# PCB.net
KiCad netlist of a schematic drawn in Altium Designer
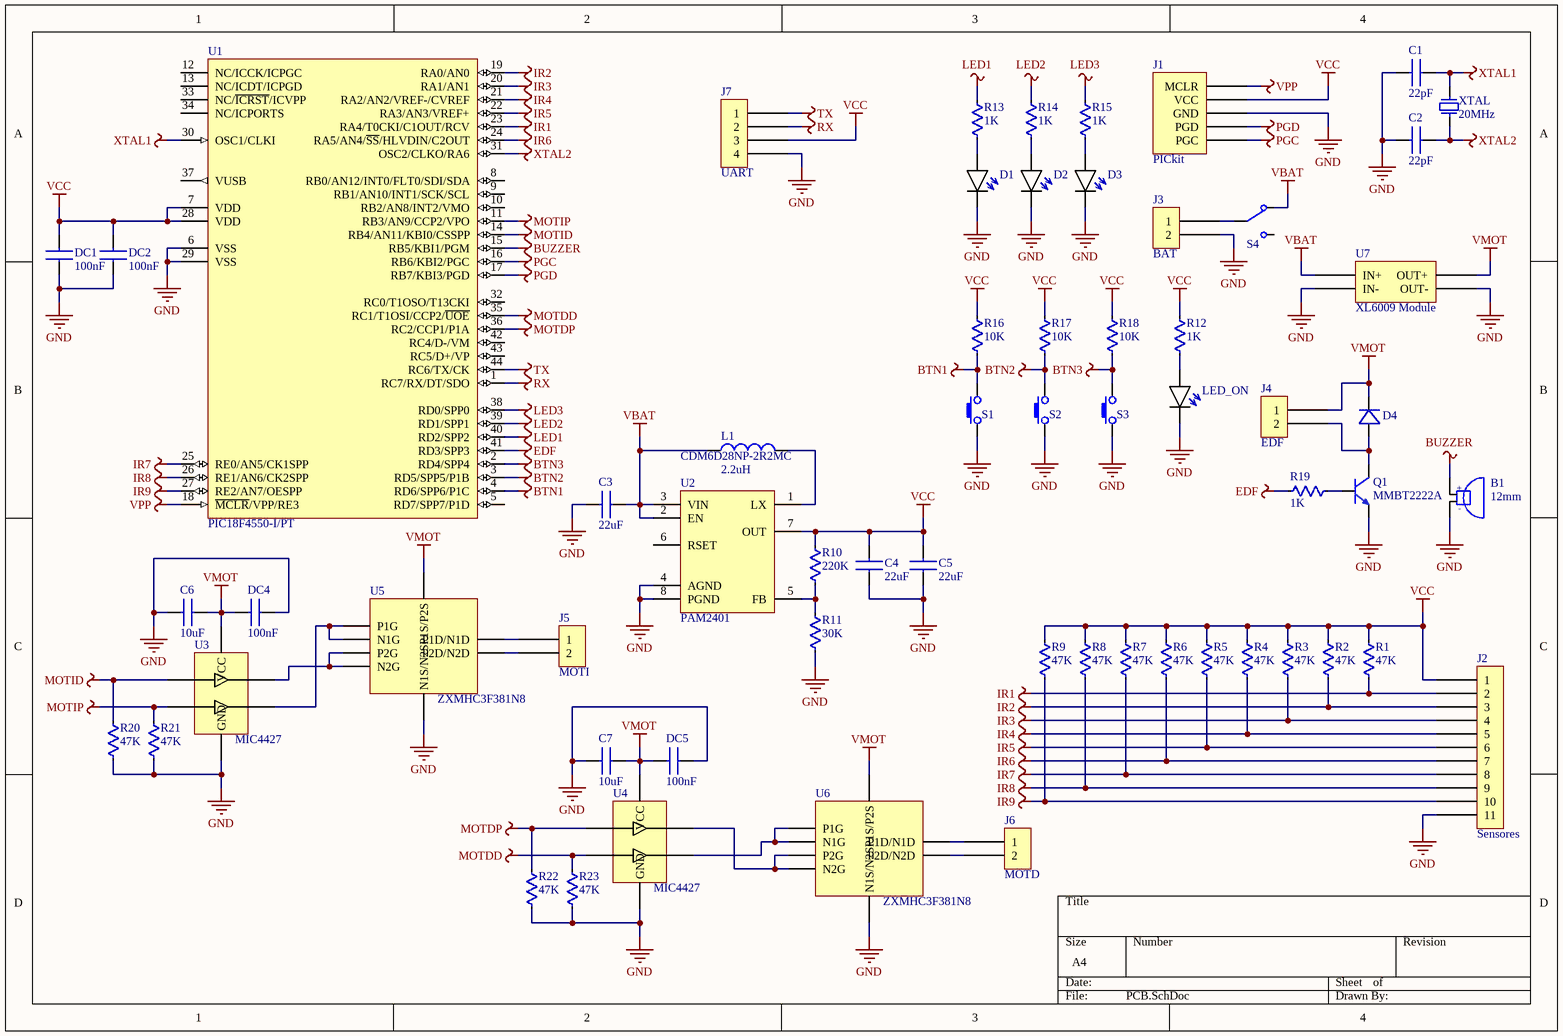
[diagram p0: PCB.SchDoc]

(export (version "E")
  (design (tool "Eeschema 10.0.6"))
  (components
    (comp (ref "B1")
      (value "12mm")
      (footprint "BUZZER-12MM")
      (libsource (lib "AltiumLibrary") (part "BUZZER-ACTIVE"))
    )
    (comp (ref "C1")
      (value "22pF")
      (footprint "C1206")
      (fields (field (name "Comment") "CAP-CER"))
      (libsource (lib "AltiumLibrary") (part "CAP-CER"))
    )
    (comp (ref "C2")
      (value "22pF")
      (footprint "C1206")
      (fields (field (name "Comment") "CAP-CER"))
      (libsource (lib "AltiumLibrary") (part "CAP-CER"))
    )
    (comp (ref "C3")
      (value "22uF")
      (footprint "C1206")
      (fields (field (name "Comment") "CAP-CER"))
      (libsource (lib "AltiumLibrary") (part "CAP-CER"))
    )
    (comp (ref "C4")
      (value "22uF")
      (footprint "C1206")
      (fields (field (name "Comment") "CAP-CER"))
      (libsource (lib "AltiumLibrary") (part "CAP-CER"))
    )
    (comp (ref "C5")
      (value "22uF")
      (footprint "C1206")
      (fields (field (name "Comment") "CAP-CER"))
      (libsource (lib "AltiumLibrary") (part "CAP-CER"))
    )
    (comp (ref "C6")
      (value "10uF")
      (footprint "C1206")
      (fields (field (name "Comment") "CAP-CER"))
      (libsource (lib "AltiumLibrary") (part "CAP-CER"))
    )
    (comp (ref "C7")
      (value "10uF")
      (footprint "C1206")
      (fields (field (name "Comment") "CAP-CER"))
      (libsource (lib "AltiumLibrary") (part "CAP-CER"))
    )
    (comp (ref "D1") (value "LED") (footprint "LED-3MM-RED") (libsource (lib "AltiumLibrary") (part "LED")))
    (comp (ref "D2")
      (value "LED")
      (footprint "LED-3MM-YELLOW")
      (libsource (lib "AltiumLibrary") (part "LED"))
    )
    (comp (ref "D3") (value "LED") (footprint "LED-3MM-GREEN") (libsource (lib "AltiumLibrary") (part "LED")))
    (comp (ref "D4") (value "1N4007") (footprint "DO-214AC") (libsource (lib "AltiumLibrary") (part "DIODE")))
    (comp (ref "DC1")
      (value "100nF")
      (footprint "C1206")
      (fields (field (name "Comment") "CAP-CER"))
      (libsource (lib "AltiumLibrary") (part "CAP-CER"))
    )
    (comp (ref "DC2")
      (value "100nF")
      (footprint "C1206")
      (fields (field (name "Comment") "CAP-CER"))
      (libsource (lib "AltiumLibrary") (part "CAP-CER"))
    )
    (comp (ref "DC4")
      (value "100nF")
      (footprint "C1206")
      (fields (field (name "Comment") "CAP-CER"))
      (libsource (lib "AltiumLibrary") (part "CAP-CER"))
    )
    (comp (ref "DC5")
      (value "100nF")
      (footprint "C1206")
      (fields (field (name "Comment") "CAP-CER"))
      (libsource (lib "AltiumLibrary") (part "CAP-CER"))
    )
    (comp (ref "J1")
      (value "PICkit")
      (footprint "Header 1x5")
      (libsource (lib "AltiumLibrary") (part "PICkit"))
    )
    (comp (ref "J2")
      (value "Sensores")
      (footprint "Header 1x11")
      (libsource (lib "AltiumLibrary") (part "Header 1x11"))
    )
    (comp (ref "J3")
      (value "BAT")
      (footprint "HEADER 1x2")
      (libsource (lib "AltiumLibrary") (part "Header 1x2"))
    )
    (comp (ref "J4")
      (value "EDF")
      (footprint "HEADER 1x2")
      (libsource (lib "AltiumLibrary") (part "Header 1x2"))
    )
    (comp (ref "J5") (value "MOTI") (footprint "HEADER 1x2") (libsource (lib "") (part "Header 1x2_1")))
    (comp (ref "J6") (value "MOTD") (footprint "HEADER 1x2") (libsource (lib "") (part "Header 1x2_1")))
    (comp (ref "J7")
      (value "UART")
      (footprint "Header 1x4")
      (libsource (lib "AltiumLibrary") (part "Header 1x4"))
    )
    (comp (ref "L1")
      (value "CDM6D28NP-2R2MC")
      (footprint "CDMC6D28")
      (fields (field (name "ALTIUM_VALUE") "2.2uH"))
      (libsource (lib "AltiumLibrary") (part "INDUCTOR"))
    )
    (comp (ref "LED_ON")
      (value "LED")
      (footprint "LED-3MM-RED")
      (libsource (lib "AltiumLibrary") (part "LED"))
    )
    (comp (ref "Q1") (value "MMBT2222A") (footprint "SOT-23") (libsource (lib "AltiumLibrary") (part "NPN")))
    (comp (ref "R1")
      (value "47K")
      (footprint "R1206")
      (fields (field (name "Comment") "RES"))
      (libsource (lib "AltiumLibrary") (part "RES"))
    )
    (comp (ref "R2")
      (value "47K")
      (footprint "R1206")
      (fields (field (name "Comment") "RES"))
      (libsource (lib "AltiumLibrary") (part "RES"))
    )
    (comp (ref "R3")
      (value "47K")
      (footprint "R1206")
      (fields (field (name "Comment") "RES"))
      (libsource (lib "AltiumLibrary") (part "RES"))
    )
    (comp (ref "R4")
      (value "47K")
      (footprint "R1206")
      (fields (field (name "Comment") "RES"))
      (libsource (lib "AltiumLibrary") (part "RES"))
    )
    (comp (ref "R5")
      (value "47K")
      (footprint "R1206")
      (fields (field (name "Comment") "RES"))
      (libsource (lib "AltiumLibrary") (part "RES"))
    )
    (comp (ref "R6")
      (value "47K")
      (footprint "R1206")
      (fields (field (name "Comment") "RES"))
      (libsource (lib "AltiumLibrary") (part "RES"))
    )
    (comp (ref "R7")
      (value "47K")
      (footprint "R1206")
      (fields (field (name "Comment") "RES"))
      (libsource (lib "AltiumLibrary") (part "RES"))
    )
    (comp (ref "R8")
      (value "47K")
      (footprint "R1206")
      (fields (field (name "Comment") "RES"))
      (libsource (lib "AltiumLibrary") (part "RES"))
    )
    (comp (ref "R9")
      (value "47K")
      (footprint "R1206")
      (fields (field (name "Comment") "RES"))
      (libsource (lib "AltiumLibrary") (part "RES"))
    )
    (comp (ref "R10")
      (value "220K")
      (footprint "R1206")
      (fields (field (name "Comment") "RES"))
      (libsource (lib "AltiumLibrary") (part "RES"))
    )
    (comp (ref "R11")
      (value "30K")
      (footprint "R1206")
      (fields (field (name "Comment") "RES"))
      (libsource (lib "AltiumLibrary") (part "RES"))
    )
    (comp (ref "R12")
      (value "1K")
      (footprint "R1206")
      (fields (field (name "Comment") "RES"))
      (libsource (lib "AltiumLibrary") (part "RES"))
    )
    (comp (ref "R13")
      (value "1K")
      (footprint "R1206")
      (fields (field (name "Comment") "RES"))
      (libsource (lib "AltiumLibrary") (part "RES"))
    )
    (comp (ref "R14")
      (value "1K")
      (footprint "R1206")
      (fields (field (name "Comment") "RES"))
      (libsource (lib "AltiumLibrary") (part "RES"))
    )
    (comp (ref "R15")
      (value "1K")
      (footprint "R1206")
      (fields (field (name "Comment") "RES"))
      (libsource (lib "AltiumLibrary") (part "RES"))
    )
    (comp (ref "R16")
      (value "10K")
      (footprint "R1206")
      (fields (field (name "Comment") "RES"))
      (libsource (lib "AltiumLibrary") (part "RES"))
    )
    (comp (ref "R17")
      (value "10K")
      (footprint "R1206")
      (fields (field (name "Comment") "RES"))
      (libsource (lib "AltiumLibrary") (part "RES"))
    )
    (comp (ref "R18")
      (value "10K")
      (footprint "R1206")
      (fields (field (name "Comment") "RES"))
      (libsource (lib "AltiumLibrary") (part "RES"))
    )
    (comp (ref "R19")
      (value "1K")
      (footprint "R1206")
      (fields (field (name "Comment") "RES"))
      (libsource (lib "") (part "RES_1"))
    )
    (comp (ref "R20")
      (value "47K")
      (footprint "R1206")
      (fields (field (name "Comment") "RES"))
      (libsource (lib "AltiumLibrary") (part "RES"))
    )
    (comp (ref "R21")
      (value "47K")
      (footprint "R1206")
      (fields (field (name "Comment") "RES"))
      (libsource (lib "AltiumLibrary") (part "RES"))
    )
    (comp (ref "R22")
      (value "47K")
      (footprint "R1206")
      (fields (field (name "Comment") "RES"))
      (libsource (lib "AltiumLibrary") (part "RES"))
    )
    (comp (ref "R23")
      (value "47K")
      (footprint "R1206")
      (fields (field (name "Comment") "RES"))
      (libsource (lib "AltiumLibrary") (part "RES"))
    )
    (comp (ref "S1")
      (value "BUTTON")
      (footprint "TACT_SWITCH-SMALL-4PIN")
      (libsource (lib "AltiumLibrary") (part "BUTTON"))
    )
    (comp (ref "S2")
      (value "BUTTON")
      (footprint "TACT_SWITCH-SMALL-4PIN")
      (libsource (lib "AltiumLibrary") (part "BUTTON"))
    )
    (comp (ref "S3")
      (value "BUTTON")
      (footprint "TACT_SWITCH-SMALL-4PIN")
      (libsource (lib "AltiumLibrary") (part "BUTTON"))
    )
    (comp (ref "S4")
      (value "SLIDE-SWITCH")
      (footprint "SWITCH")
      (libsource (lib "AltiumLibrary") (part "SLIDE-SWITCH"))
    )
    (comp (ref "U1")
      (value "PIC18F4550-I/PT")
      (footprint "TQFP-PT44_L")
      (fields (field (name "PUBLISHER") "Altium Limited"))
      (libsource (lib "AltiumLibrary") (part "PIC18F4550-I/PT"))
    )
    (comp (ref "U2")
      (value "PAM2401")
      (footprint "MSOP-8")
      (libsource (lib "AltiumLibrary") (part "PAM2401"))
    )
    (comp (ref "U3") (value "MIC4427") (footprint "SOIC-8") (libsource (lib "AltiumLibrary") (part "4427")))
    (comp (ref "U4") (value "MIC4427") (footprint "SOIC-8") (libsource (lib "AltiumLibrary") (part "4427")))
    (comp (ref "U5")
      (value "ZXMHC3F381N8")
      (footprint "SOIC-8")
      (libsource (lib "AltiumLibrary") (part "ZXMHC3F381N8"))
    )
    (comp (ref "U6")
      (value "ZXMHC3F381N8")
      (footprint "SOIC-8")
      (libsource (lib "AltiumLibrary") (part "ZXMHC3F381N8"))
    )
    (comp (ref "U7")
      (value "XL6009 Module")
      (footprint "XL6009 mdl")
      (libsource (lib "AltiumLibrary") (part "XL6009 Module"))
    )
    (comp (ref "XTAL")
      (value "XTAL")
      (footprint "HC-49/S")
      (fields (field (name "FREQUENCY") "20MHz"))
      (libsource (lib "AltiumLibrary") (part "XTAL"))
    )
  )
  (nets
    (net (code "1") (name "BTN1") (class "Default")
      (node (ref "R16") (pin "1") (pintype "passive"))
      (node (ref "S1") (pin "2") (pintype "passive"))
      (node (ref "U1") (pin "4") (pinfunction "RD6/SPP6/P1C_4") (pintype "bidirectional"))
    )
    (net (code "2") (name "BTN2") (class "Default")
      (node (ref "R17") (pin "1") (pintype "passive"))
      (node (ref "S2") (pin "2") (pintype "passive"))
      (node (ref "U1") (pin "3") (pinfunction "RD5/SPP5/P1B_3") (pintype "bidirectional"))
    )
    (net (code "3") (name "BTN3") (class "Default")
      (node (ref "R18") (pin "1") (pintype "passive"))
      (node (ref "S3") (pin "2") (pintype "passive"))
      (node (ref "U1") (pin "2") (pinfunction "RD4/SPP4_2") (pintype "bidirectional"))
    )
    (net (code "4") (name "BUZZER") (class "Default")
      (node (ref "B1") (pin "1") (pinfunction "+_1") (pintype "passive"))
      (node (ref "U1") (pin "15") (pinfunction "RB5/KBI1/PGM_15") (pintype "bidirectional"))
    )
    (net (code "5") (name "EDF") (class "Default")
      (node (ref "R19") (pin "1") (pintype "passive"))
      (node (ref "U1") (pin "41") (pinfunction "RD3/SPP3_41") (pintype "bidirectional"))
    )
    (net (code "6") (name "GND") (class "Default")
      (node (ref "B1") (pin "2") (pinfunction "-_2") (pintype "passive"))
      (node (ref "C1") (pin "1") (pintype "passive"))
      (node (ref "C2") (pin "1") (pintype "passive"))
      (node (ref "C3") (pin "1") (pintype "passive"))
      (node (ref "C4") (pin "1") (pintype "passive"))
      (node (ref "C5") (pin "1") (pintype "passive"))
      (node (ref "C6") (pin "2") (pintype "passive"))
      (node (ref "C7") (pin "2") (pintype "passive"))
      (node (ref "D1") (pin "K") (pintype "passive"))
      (node (ref "D2") (pin "K") (pintype "passive"))
      (node (ref "D3") (pin "K") (pintype "passive"))
      (node (ref "DC1") (pin "1") (pintype "passive"))
      (node (ref "DC2") (pin "1") (pintype "passive"))
      (node (ref "DC4") (pin "2") (pintype "passive"))
      (node (ref "DC5") (pin "2") (pintype "passive"))
      (node (ref "J1") (pin "3") (pinfunction "GND_3") (pintype "power_in"))
      (node (ref "J2") (pin "11") (pinfunction "11_11") (pintype "passive"))
      (node (ref "J3") (pin "2") (pinfunction "2_2") (pintype "passive"))
      (node (ref "J7") (pin "4") (pinfunction "4_4") (pintype "passive"))
      (node (ref "LED_ON") (pin "K") (pintype "passive"))
      (node (ref "Q1") (pin "E") (pinfunction "E_E") (pintype "passive"))
      (node (ref "R11") (pin "1") (pintype "passive"))
      (node (ref "R20") (pin "1") (pintype "passive"))
      (node (ref "R21") (pin "1") (pintype "passive"))
      (node (ref "R22") (pin "1") (pintype "passive"))
      (node (ref "R23") (pin "1") (pintype "passive"))
      (node (ref "S1") (pin "1") (pintype "passive"))
      (node (ref "S2") (pin "1") (pintype "passive"))
      (node (ref "S3") (pin "1") (pintype "passive"))
      (node (ref "U1") (pin "29") (pinfunction "VSS_29") (pintype "power_in"))
      (node (ref "U1") (pin "6") (pinfunction "VSS_6") (pintype "power_in"))
      (node (ref "U2") (pin "4") (pinfunction "AGND_4") (pintype "passive"))
      (node (ref "U2") (pin "8") (pinfunction "PGND_8") (pintype "passive"))
      (node (ref "U3") (pin "3") (pinfunction "GND_3") (pintype "passive"))
      (node (ref "U4") (pin "3") (pinfunction "GND_3") (pintype "passive"))
      (node (ref "U5") (pin "3") (pinfunction "N1S/N2S_3") (pintype "passive"))
      (node (ref "U6") (pin "3") (pinfunction "N1S/N2S_3") (pintype "passive"))
      (node (ref "U7") (pin "1") (pinfunction "IN-_1") (pintype "passive"))
      (node (ref "U7") (pin "2") (pinfunction "OUT-_2") (pintype "passive"))
    )
    (net (code "7") (name "IR1") (class "Default")
      (node (ref "J2") (pin "2") (pinfunction "2_2") (pintype "passive"))
      (node (ref "R1") (pin "1") (pintype "passive"))
      (node (ref "U1") (pin "23") (pinfunction "RA4/T0CKI/C1OUT/RCV_23") (pintype "bidirectional"))
    )
    (net (code "8") (name "IR2") (class "Default")
      (node (ref "J2") (pin "3") (pinfunction "3_3") (pintype "passive"))
      (node (ref "R2") (pin "1") (pintype "passive"))
      (node (ref "U1") (pin "19") (pinfunction "RA0/AN0_19") (pintype "bidirectional"))
    )
    (net (code "9") (name "IR3") (class "Default")
      (node (ref "J2") (pin "4") (pinfunction "4_4") (pintype "passive"))
      (node (ref "R3") (pin "1") (pintype "passive"))
      (node (ref "U1") (pin "20") (pinfunction "RA1/AN1_20") (pintype "bidirectional"))
    )
    (net (code "10") (name "IR4") (class "Default")
      (node (ref "J2") (pin "5") (pinfunction "5_5") (pintype "passive"))
      (node (ref "R4") (pin "1") (pintype "passive"))
      (node (ref "U1") (pin "21") (pinfunction "RA2/AN2/VREF-/CVREF_21") (pintype "bidirectional"))
    )
    (net (code "11") (name "IR5") (class "Default")
      (node (ref "J2") (pin "6") (pinfunction "6_6") (pintype "passive"))
      (node (ref "R5") (pin "1") (pintype "passive"))
      (node (ref "U1") (pin "22") (pinfunction "RA3/AN3/VREF+_22") (pintype "bidirectional"))
    )
    (net (code "12") (name "IR6") (class "Default")
      (node (ref "J2") (pin "7") (pinfunction "7_7") (pintype "passive"))
      (node (ref "R6") (pin "1") (pintype "passive"))
      (node (ref "U1") (pin "24") (pinfunction "RA5/AN4/~{SS}/HLVDIN/C2OUT_24") (pintype "bidirectional"))
    )
    (net (code "13") (name "IR7") (class "Default")
      (node (ref "J2") (pin "8") (pinfunction "8_8") (pintype "passive"))
      (node (ref "R7") (pin "1") (pintype "passive"))
      (node (ref "U1") (pin "25") (pinfunction "RE0/AN5/CK1SPP_25") (pintype "bidirectional"))
    )
    (net (code "14") (name "IR8") (class "Default")
      (node (ref "J2") (pin "9") (pinfunction "9_9") (pintype "passive"))
      (node (ref "R8") (pin "1") (pintype "passive"))
      (node (ref "U1") (pin "26") (pinfunction "RE1/AN6/CK2SPP_26") (pintype "bidirectional"))
    )
    (net (code "15") (name "IR9") (class "Default")
      (node (ref "J2") (pin "10") (pinfunction "10_10") (pintype "passive"))
      (node (ref "R9") (pin "1") (pintype "passive"))
      (node (ref "U1") (pin "27") (pinfunction "RE2/AN7/OESPP_27") (pintype "bidirectional"))
    )
    (net (code "16") (name "LED1") (class "Default")
      (node (ref "R13") (pin "2") (pintype "passive"))
      (node (ref "U1") (pin "40") (pinfunction "RD2/SPP2_40") (pintype "bidirectional"))
    )
    (net (code "17") (name "LED2") (class "Default")
      (node (ref "R14") (pin "2") (pintype "passive"))
      (node (ref "U1") (pin "39") (pinfunction "RD1/SPP1_39") (pintype "bidirectional"))
    )
    (net (code "18") (name "LED3") (class "Default")
      (node (ref "R15") (pin "2") (pintype "passive"))
      (node (ref "U1") (pin "38") (pinfunction "RD0/SPP0_38") (pintype "bidirectional"))
    )
    (net (code "19") (name "MOTDD") (class "Default")
      (node (ref "R23") (pin "2") (pintype "passive"))
      (node (ref "U1") (pin "35") (pinfunction "RC1/T1OSI/CCP2/~{UOE}_35") (pintype "bidirectional"))
      (node (ref "U4") (pin "4") (pinfunction "INB_4") (pintype "passive"))
    )
    (net (code "20") (name "MOTDP") (class "Default")
      (node (ref "R22") (pin "2") (pintype "passive"))
      (node (ref "U1") (pin "36") (pinfunction "RC2/CCP1/P1A_36") (pintype "bidirectional"))
      (node (ref "U4") (pin "2") (pinfunction "INA_2") (pintype "passive"))
    )
    (net (code "21") (name "MOTID") (class "Default")
      (node (ref "R20") (pin "2") (pintype "passive"))
      (node (ref "U1") (pin "14") (pinfunction "RB4/AN11/KBI0/CSSPP_14") (pintype "bidirectional"))
      (node (ref "U3") (pin "2") (pinfunction "INA_2") (pintype "passive"))
    )
    (net (code "22") (name "MOTIP") (class "Default")
      (node (ref "R21") (pin "2") (pintype "passive"))
      (node (ref "U1") (pin "11") (pinfunction "RB3/AN9/CCP2/VPO_11") (pintype "bidirectional"))
      (node (ref "U3") (pin "4") (pinfunction "INB_4") (pintype "passive"))
    )
    (net (code "23") (name "Net-(D1-PadA)") (class "Default")
      (node (ref "D1") (pin "A") (pintype "passive"))
      (node (ref "R13") (pin "1") (pintype "passive"))
    )
    (net (code "24") (name "Net-(D2-PadA)") (class "Default")
      (node (ref "D2") (pin "A") (pintype "passive"))
      (node (ref "R14") (pin "1") (pintype "passive"))
    )
    (net (code "25") (name "Net-(D3-PadA)") (class "Default")
      (node (ref "D3") (pin "A") (pintype "passive"))
      (node (ref "R15") (pin "1") (pintype "passive"))
    )
    (net (code "26") (name "Net-(D4-PadA)") (class "Default")
      (node (ref "D4") (pin "A") (pintype "passive"))
      (node (ref "J4") (pin "2") (pinfunction "2_2") (pintype "passive"))
      (node (ref "Q1") (pin "C") (pinfunction "C_C") (pintype "passive"))
    )
    (net (code "27") (name "Net-(J3-Pad1)") (class "Default")
      (node (ref "J3") (pin "1") (pinfunction "1_1") (pintype "passive"))
      (node (ref "S4") (pin "2") (pintype "power_in"))
    )
    (net (code "28") (name "Net-(LED_ON-PadA)") (class "Default")
      (node (ref "LED_ON") (pin "A") (pintype "passive"))
      (node (ref "R12") (pin "1") (pintype "passive"))
    )
    (net (code "29") (name "Net-(Q1-PadB)") (class "Default")
      (node (ref "Q1") (pin "B") (pinfunction "B_B") (pintype "passive"))
      (node (ref "R19") (pin "2") (pintype "passive"))
    )
    (net (code "30") (name "Net-(U2-FB)") (class "Default")
      (node (ref "R10") (pin "1") (pintype "passive"))
      (node (ref "R11") (pin "2") (pintype "passive"))
      (node (ref "U2") (pin "5") (pinfunction "FB_5") (pintype "passive"))
    )
    (net (code "31") (name "Net-(U2-LX)") (class "Default")
      (node (ref "L1") (pin "2") (pinfunction "2_2") (pintype "passive"))
      (node (ref "U2") (pin "1") (pinfunction "LX_1") (pintype "passive"))
    )
    (net (code "32") (name "Net-(U3-OUTA)") (class "Default")
      (node (ref "U3") (pin "7") (pinfunction "OUTA_7") (pintype "passive"))
      (node (ref "U5") (pin "4") (pinfunction "N2G_4") (pintype "passive"))
      (node (ref "U5") (pin "5") (pinfunction "P2G_5") (pintype "passive"))
    )
    (net (code "33") (name "Net-(U3-OUTB)") (class "Default")
      (node (ref "U3") (pin "5") (pinfunction "OUTB_5") (pintype "passive"))
      (node (ref "U5") (pin "1") (pinfunction "N1G_1") (pintype "passive"))
      (node (ref "U5") (pin "8") (pinfunction "P1G_8") (pintype "passive"))
    )
    (net (code "34") (name "Net-(U4-OUTA)") (class "Default")
      (node (ref "U4") (pin "7") (pinfunction "OUTA_7") (pintype "passive"))
      (node (ref "U6") (pin "4") (pinfunction "N2G_4") (pintype "passive"))
      (node (ref "U6") (pin "5") (pinfunction "P2G_5") (pintype "passive"))
    )
    (net (code "35") (name "Net-(U4-OUTB)") (class "Default")
      (node (ref "U4") (pin "5") (pinfunction "OUTB_5") (pintype "passive"))
      (node (ref "U6") (pin "1") (pinfunction "N1G_1") (pintype "passive"))
      (node (ref "U6") (pin "8") (pinfunction "P1G_8") (pintype "passive"))
    )
    (net (code "36") (name "Net-(U5-P1D{slash}N1D)") (class "Default")
      (node (ref "J5") (pin "1") (pinfunction "1_1") (pintype "passive"))
      (node (ref "U5") (pin "2") (pinfunction "P1D/N1D_2") (pintype "passive"))
    )
    (net (code "37") (name "Net-(U5-P2D{slash}N2D)") (class "Default")
      (node (ref "J5") (pin "2") (pinfunction "2_2") (pintype "passive"))
      (node (ref "U5") (pin "6") (pinfunction "P2D/N2D_6") (pintype "passive"))
    )
    (net (code "38") (name "Net-(U6-P1D{slash}N1D)") (class "Default")
      (node (ref "J6") (pin "1") (pinfunction "1_1") (pintype "passive"))
      (node (ref "U6") (pin "2") (pinfunction "P1D/N1D_2") (pintype "passive"))
    )
    (net (code "39") (name "Net-(U6-P2D{slash}N2D)") (class "Default")
      (node (ref "J6") (pin "2") (pinfunction "2_2") (pintype "passive"))
      (node (ref "U6") (pin "6") (pinfunction "P2D/N2D_6") (pintype "passive"))
    )
    (net (code "40") (name "PGC") (class "Default")
      (node (ref "J1") (pin "5") (pinfunction "PGC_5") (pintype "passive"))
      (node (ref "U1") (pin "16") (pinfunction "RB6/KBI2/PGC_16") (pintype "bidirectional"))
    )
    (net (code "41") (name "PGD") (class "Default")
      (node (ref "J1") (pin "4") (pinfunction "PGD_4") (pintype "passive"))
      (node (ref "U1") (pin "17") (pinfunction "RB7/KBI3/PGD_17") (pintype "bidirectional"))
    )
    (net (code "42") (name "RX") (class "Default")
      (node (ref "J7") (pin "2") (pinfunction "2_2") (pintype "passive"))
      (node (ref "U1") (pin "1") (pinfunction "RC7/RX/DT/SDO_1") (pintype "bidirectional"))
    )
    (net (code "43") (name "TX") (class "Default")
      (node (ref "J7") (pin "1") (pinfunction "1_1") (pintype "passive"))
      (node (ref "U1") (pin "44") (pinfunction "RC6/TX/CK_44") (pintype "bidirectional"))
    )
    (net (code "44") (name "VBAT") (class "Default")
      (node (ref "C3") (pin "2") (pintype "passive"))
      (node (ref "L1") (pin "1") (pinfunction "1_1") (pintype "passive"))
      (node (ref "S4") (pin "1") (pintype "power_in"))
      (node (ref "U2") (pin "2") (pinfunction "EN_2") (pintype "passive"))
      (node (ref "U2") (pin "3") (pinfunction "VIN_3") (pintype "passive"))
      (node (ref "U7") (pin "0") (pinfunction "IN+_0") (pintype "passive"))
    )
    (net (code "45") (name "VCC") (class "Default")
      (node (ref "C4") (pin "2") (pintype "passive"))
      (node (ref "C5") (pin "2") (pintype "passive"))
      (node (ref "DC1") (pin "2") (pintype "passive"))
      (node (ref "DC2") (pin "2") (pintype "passive"))
      (node (ref "J1") (pin "2") (pinfunction "VCC_2") (pintype "power_in"))
      (node (ref "J2") (pin "1") (pinfunction "1_1") (pintype "passive"))
      (node (ref "J7") (pin "3") (pinfunction "3_3") (pintype "passive"))
      (node (ref "R1") (pin "2") (pintype "passive"))
      (node (ref "R10") (pin "2") (pintype "passive"))
      (node (ref "R12") (pin "2") (pintype "passive"))
      (node (ref "R16") (pin "2") (pintype "passive"))
      (node (ref "R17") (pin "2") (pintype "passive"))
      (node (ref "R18") (pin "2") (pintype "passive"))
      (node (ref "R2") (pin "2") (pintype "passive"))
      (node (ref "R3") (pin "2") (pintype "passive"))
      (node (ref "R4") (pin "2") (pintype "passive"))
      (node (ref "R5") (pin "2") (pintype "passive"))
      (node (ref "R6") (pin "2") (pintype "passive"))
      (node (ref "R7") (pin "2") (pintype "passive"))
      (node (ref "R8") (pin "2") (pintype "passive"))
      (node (ref "R9") (pin "2") (pintype "passive"))
      (node (ref "U1") (pin "28") (pinfunction "VDD_28") (pintype "power_in"))
      (node (ref "U1") (pin "7") (pinfunction "VDD_7") (pintype "power_in"))
      (node (ref "U2") (pin "7") (pinfunction "OUT_7") (pintype "passive"))
    )
    (net (code "46") (name "VMOT") (class "Default")
      (node (ref "C6") (pin "1") (pintype "passive"))
      (node (ref "C7") (pin "1") (pintype "passive"))
      (node (ref "D4") (pin "K") (pintype "passive"))
      (node (ref "DC4") (pin "1") (pintype "passive"))
      (node (ref "DC5") (pin "1") (pintype "passive"))
      (node (ref "J4") (pin "1") (pinfunction "1_1") (pintype "passive"))
      (node (ref "U3") (pin "6") (pinfunction "VCC_6") (pintype "passive"))
      (node (ref "U4") (pin "6") (pinfunction "VCC_6") (pintype "passive"))
      (node (ref "U5") (pin "7") (pinfunction "P1S/P2S_7") (pintype "passive"))
      (node (ref "U6") (pin "7") (pinfunction "P1S/P2S_7") (pintype "passive"))
      (node (ref "U7") (pin "3") (pinfunction "OUT+_3") (pintype "passive"))
    )
    (net (code "47") (name "VPP") (class "Default")
      (node (ref "J1") (pin "1") (pinfunction "MCLR_1") (pintype "passive"))
      (node (ref "U1") (pin "18") (pinfunction "~{MCLR}/VPP/RE3_18") (pintype "input"))
    )
    (net (code "48") (name "XTAL1") (class "Default")
      (node (ref "C1") (pin "2") (pintype "passive"))
      (node (ref "U1") (pin "30") (pinfunction "OSC1/CLKI_30") (pintype "input"))
      (node (ref "XTAL") (pin "2") (pintype "passive"))
    )
    (net (code "49") (name "XTAL2") (class "Default")
      (node (ref "C2") (pin "2") (pintype "passive"))
      (node (ref "U1") (pin "31") (pinfunction "OSC2/CLKO/RA6_31") (pintype "bidirectional"))
      (node (ref "XTAL") (pin "1") (pintype "passive"))
    )
    (net (code "50") (name "unconnected-(S4-Pad3)") (class "Default")
      (node (ref "S4") (pin "3") (pintype "power_in"))
    )
    (net (code "51") (name "unconnected-(U1-NC{slash}ICCK{slash}ICPGC-Pad12)") (class "Default")
      (node (ref "U1") (pin "12") (pinfunction "NC/ICCK/ICPGC_12") (pintype "passive"))
    )
    (net (code "52") (name "unconnected-(U1-NC{slash}ICDT{slash}ICPGD-Pad13)") (class "Default")
      (node (ref "U1") (pin "13") (pinfunction "NC/ICDT/ICPGD_13") (pintype "passive"))
    )
    (net (code "53") (name "unconnected-(U1-NC{slash}ICPORTS-Pad34)") (class "Default")
      (node (ref "U1") (pin "34") (pinfunction "NC/ICPORTS_34") (pintype "passive"))
    )
    (net (code "54") (name "unconnected-(U1-NC{slash}~{ICRST}{slash}ICVPP-Pad33)") (class "Default")
      (node (ref "U1") (pin "33") (pinfunction "NC/~{ICRST}/ICVPP_33") (pintype "passive"))
    )
    (net (code "55") (name "unconnected-(U1-RB0{slash}AN12{slash}INT0{slash}FLT0{slash}SDI{slash}SDA-Pad8)") (class "Default")
      (node (ref "U1") (pin "8") (pinfunction "RB0/AN12/INT0/FLT0/SDI/SDA_8") (pintype "bidirectional"))
    )
    (net (code "56") (name "unconnected-(U1-RB1{slash}AN10{slash}INT1{slash}SCK{slash}SCL-Pad9)") (class "Default")
      (node (ref "U1") (pin "9") (pinfunction "RB1/AN10/INT1/SCK/SCL_9") (pintype "bidirectional"))
    )
    (net (code "57") (name "unconnected-(U1-RB2{slash}AN8{slash}INT2{slash}VMO-Pad10)") (class "Default")
      (node (ref "U1") (pin "10") (pinfunction "RB2/AN8/INT2/VMO_10") (pintype "bidirectional"))
    )
    (net (code "58") (name "unconnected-(U1-RC0{slash}T1OSO{slash}T13CKI-Pad32)") (class "Default")
      (node (ref "U1") (pin "32") (pinfunction "RC0/T1OSO/T13CKI_32") (pintype "bidirectional"))
    )
    (net (code "59") (name "unconnected-(U1-RC4{slash}D-{slash}VM-Pad42)") (class "Default")
      (node (ref "U1") (pin "42") (pinfunction "RC4/D-/VM_42") (pintype "bidirectional"))
    )
    (net (code "60") (name "unconnected-(U1-RC5{slash}D+{slash}VP-Pad43)") (class "Default")
      (node (ref "U1") (pin "43") (pinfunction "RC5/D+/VP_43") (pintype "bidirectional"))
    )
    (net (code "61") (name "unconnected-(U1-RD7{slash}SPP7{slash}P1D-Pad5)") (class "Default")
      (node (ref "U1") (pin "5") (pinfunction "RD7/SPP7/P1D_5") (pintype "bidirectional"))
    )
    (net (code "62") (name "unconnected-(U1-VUSB-Pad37)") (class "Default")
      (node (ref "U1") (pin "37") (pinfunction "VUSB_37") (pintype "output"))
    )
    (net (code "63") (name "unconnected-(U2-RSET-Pad6)") (class "Default")
      (node (ref "U2") (pin "6") (pinfunction "RSET_6") (pintype "passive"))
    )
  )
)
